# P_05__PMIC.net
KiCad netlist of a schematic drawn in Altium Designer
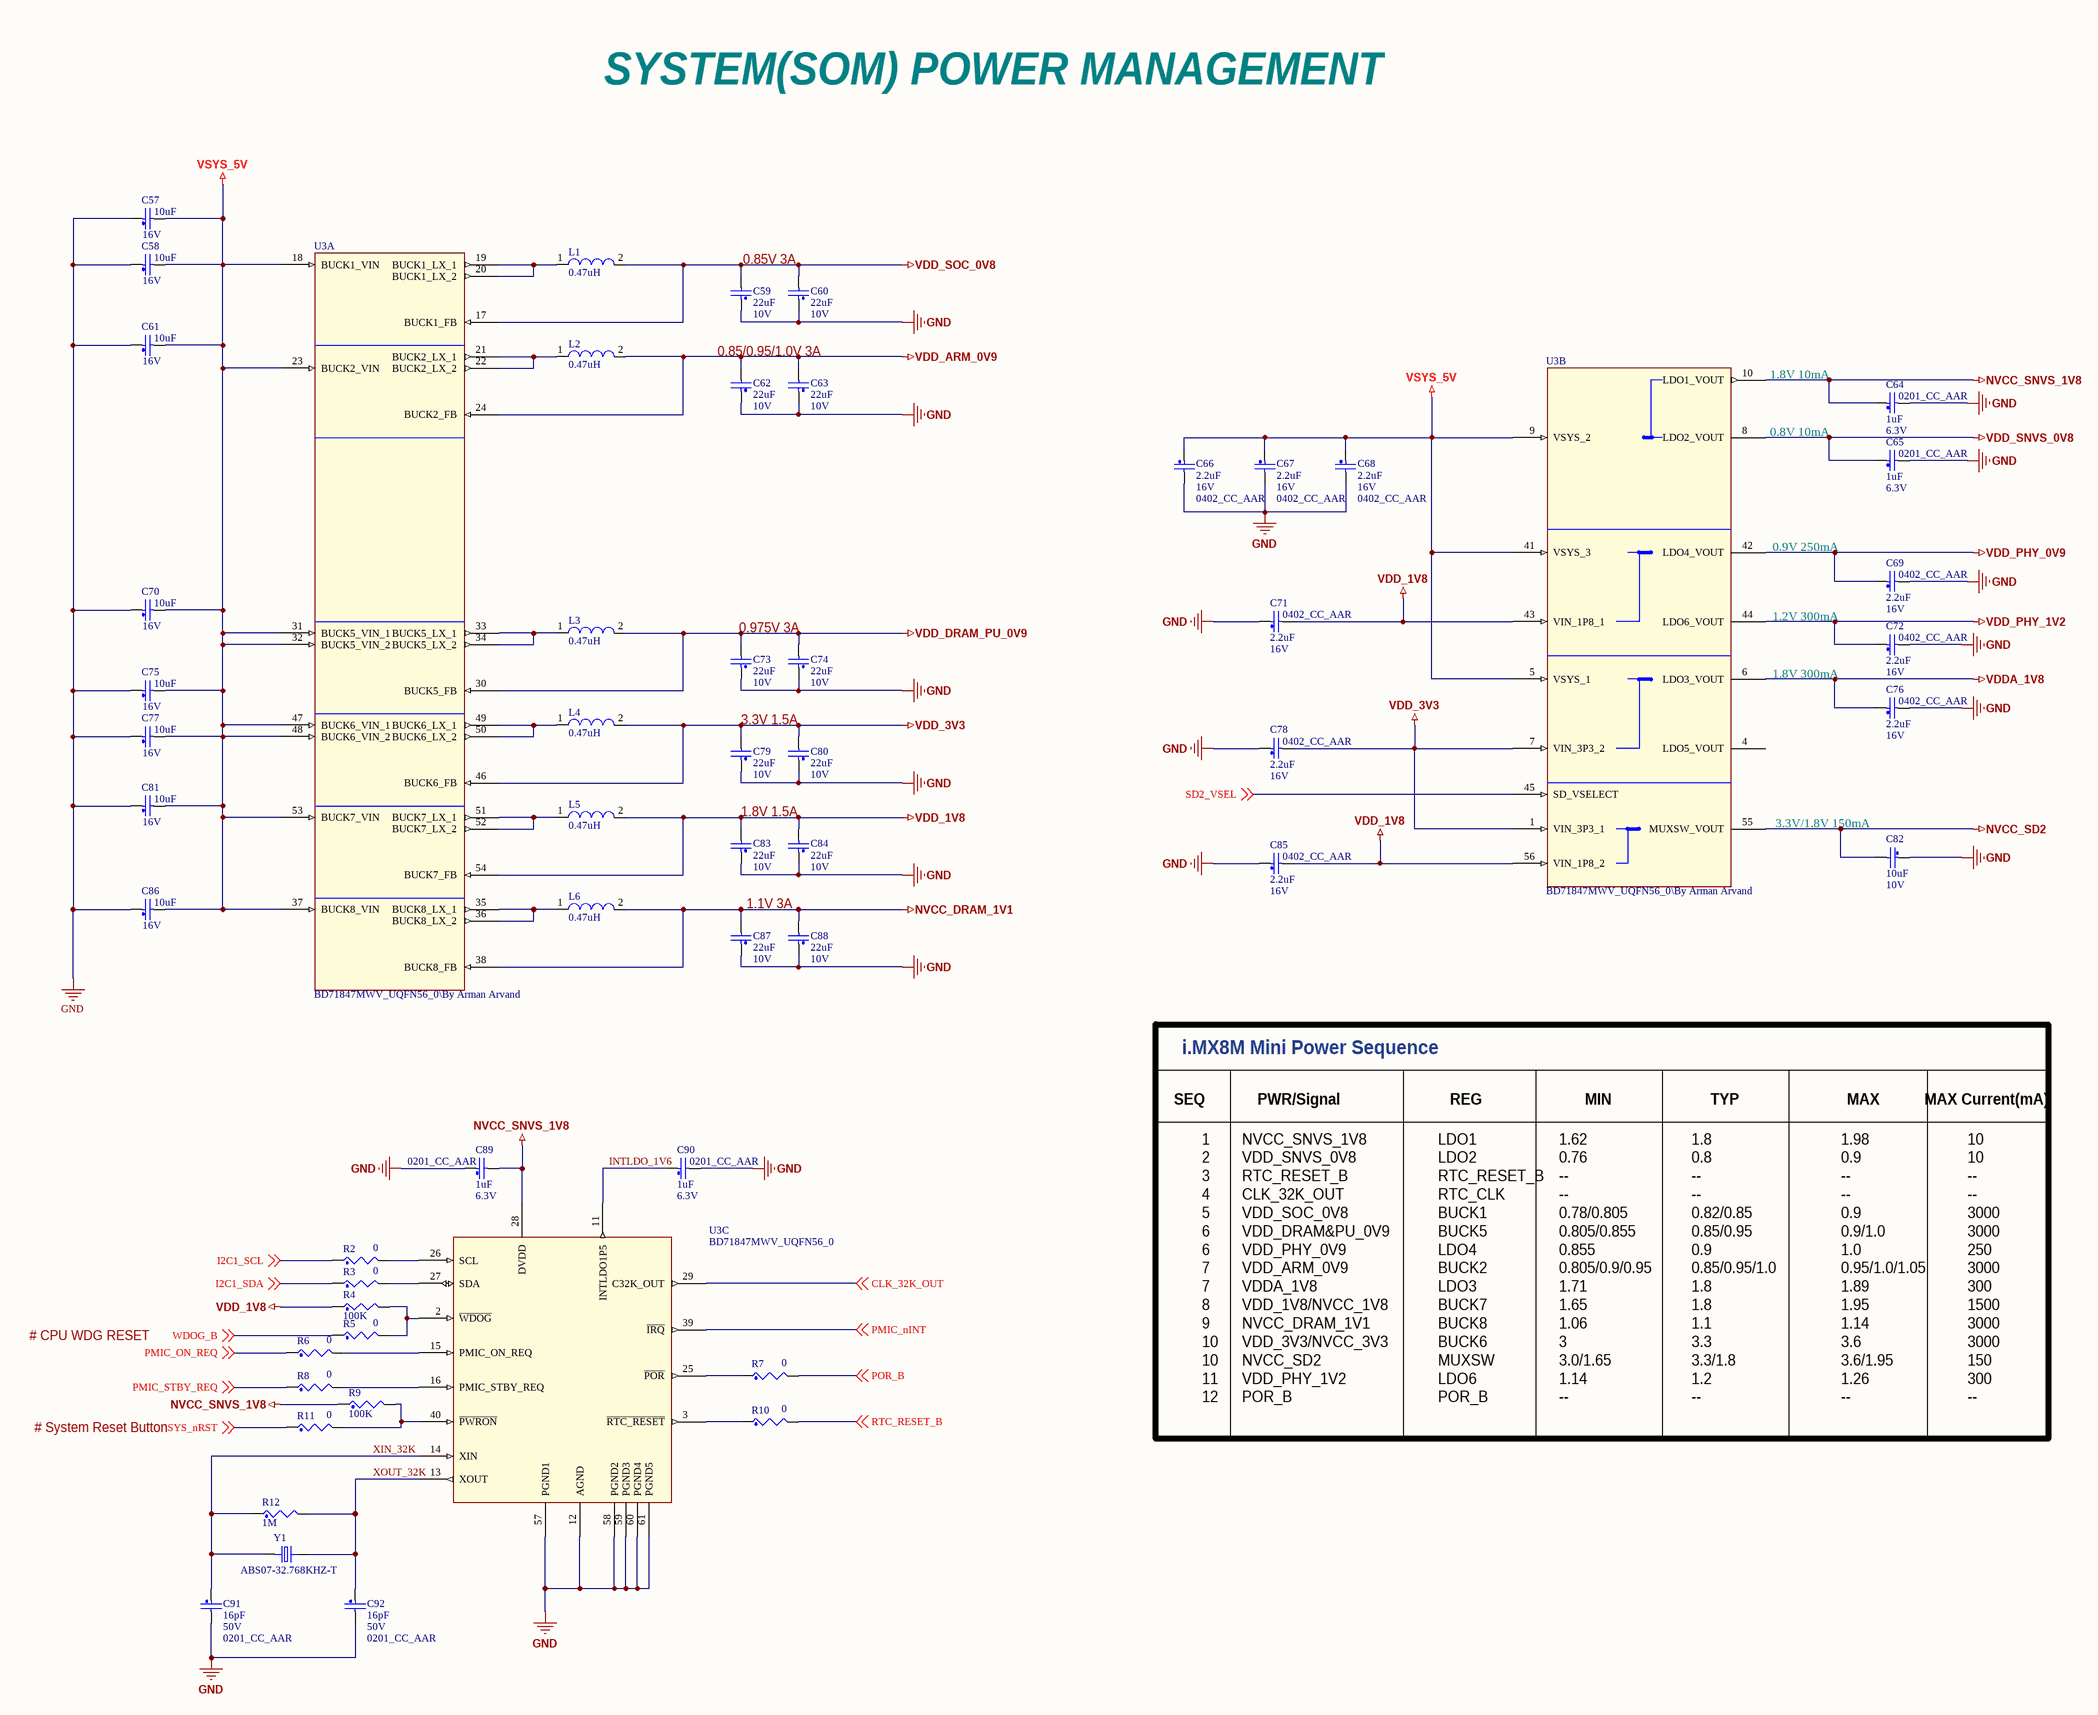
[diagram p0: P[05]_PMIC.SchDoc]

(export (version "E")
  (design (tool "Eeschema 10.0.6"))
  (components
    (comp (ref "C57")
      (value "10uF")
      (footprint "0603_CC")
      (fields (field (name "VOLTAGE") "16V"))
      (libsource (lib "AA_iMX8_M_") (part "CAP_NP"))
    )
    (comp (ref "C58")
      (value "10uF")
      (footprint "0603_CC")
      (fields (field (name "VOLTAGE") "16V"))
      (libsource (lib "AA_iMX8_M_") (part "CAP_NP"))
    )
    (comp (ref "C59")
      (value "22uF")
      (footprint "0603_CC")
      (fields (field (name "VOLTAGE") "10V"))
      (libsource (lib "AA_iMX8_M_") (part "CAP_NP"))
    )
    (comp (ref "C60")
      (value "22uF")
      (footprint "0603_CC")
      (fields (field (name "VOLTAGE") "10V"))
      (libsource (lib "AA_iMX8_M_") (part "CAP_NP"))
    )
    (comp (ref "C61")
      (value "10uF")
      (footprint "0603_CC")
      (fields (field (name "VOLTAGE") "16V"))
      (libsource (lib "AA_iMX8_M_") (part "CAP_NP"))
    )
    (comp (ref "C62")
      (value "22uF")
      (footprint "0603_CC")
      (fields (field (name "VOLTAGE") "10V"))
      (libsource (lib "AA_iMX8_M_") (part "CAP_NP"))
    )
    (comp (ref "C63")
      (value "22uF")
      (footprint "0603_CC")
      (fields (field (name "VOLTAGE") "10V"))
      (libsource (lib "AA_iMX8_M_") (part "CAP_NP"))
    )
    (comp (ref "C64")
      (value "1uF")
      (footprint "0201_CC_AAR")
      (fields (field (name "VOLTAGE") "6.3V"))
      (libsource (lib "AA_iMX8_M_") (part "CAP_NP"))
    )
    (comp (ref "C65")
      (value "1uF")
      (footprint "0201_CC_AAR")
      (fields (field (name "VOLTAGE") "6.3V"))
      (libsource (lib "AA_iMX8_M_") (part "CAP_NP"))
    )
    (comp (ref "C66")
      (value "2.2uF")
      (footprint "0402_CC_AAR")
      (fields (field (name "VOLTAGE") "16V"))
      (libsource (lib "AA_iMX8_M_") (part "CAP_NP"))
    )
    (comp (ref "C67")
      (value "2.2uF")
      (footprint "0402_CC_AAR")
      (fields (field (name "VOLTAGE") "16V"))
      (libsource (lib "AA_iMX8_M_") (part "CAP_NP"))
    )
    (comp (ref "C68")
      (value "2.2uF")
      (footprint "0402_CC_AAR")
      (fields (field (name "VOLTAGE") "16V"))
      (libsource (lib "AA_iMX8_M_") (part "CAP_NP"))
    )
    (comp (ref "C69")
      (value "2.2uF")
      (footprint "0402_CC_AAR")
      (fields (field (name "VOLTAGE") "16V"))
      (libsource (lib "AA_iMX8_M_") (part "CAP_NP"))
    )
    (comp (ref "C70")
      (value "10uF")
      (footprint "0603_CC")
      (fields (field (name "VOLTAGE") "16V"))
      (libsource (lib "AA_iMX8_M_") (part "CAP_NP"))
    )
    (comp (ref "C71")
      (value "2.2uF")
      (footprint "0402_CC_AAR")
      (fields (field (name "VOLTAGE") "16V"))
      (libsource (lib "AA_iMX8_M_") (part "CAP_NP"))
    )
    (comp (ref "C72")
      (value "2.2uF")
      (footprint "0402_CC_AAR")
      (fields (field (name "VOLTAGE") "16V"))
      (libsource (lib "AA_iMX8_M_") (part "CAP_NP"))
    )
    (comp (ref "C73")
      (value "22uF")
      (footprint "0603_CC")
      (fields (field (name "VOLTAGE") "10V"))
      (libsource (lib "AA_iMX8_M_") (part "CAP_NP"))
    )
    (comp (ref "C74")
      (value "22uF")
      (footprint "0603_CC")
      (fields (field (name "VOLTAGE") "10V"))
      (libsource (lib "AA_iMX8_M_") (part "CAP_NP"))
    )
    (comp (ref "C75")
      (value "10uF")
      (footprint "0603_CC")
      (fields (field (name "VOLTAGE") "16V"))
      (libsource (lib "AA_iMX8_M_") (part "CAP_NP"))
    )
    (comp (ref "C76")
      (value "2.2uF")
      (footprint "0402_CC_AAR")
      (fields (field (name "VOLTAGE") "16V"))
      (libsource (lib "AA_iMX8_M_") (part "CAP_NP"))
    )
    (comp (ref "C77")
      (value "10uF")
      (footprint "0603_CC")
      (fields (field (name "VOLTAGE") "16V"))
      (libsource (lib "AA_iMX8_M_") (part "CAP_NP"))
    )
    (comp (ref "C78")
      (value "2.2uF")
      (footprint "0402_CC_AAR")
      (fields (field (name "VOLTAGE") "16V"))
      (libsource (lib "AA_iMX8_M_") (part "CAP_NP"))
    )
    (comp (ref "C79")
      (value "22uF")
      (footprint "0603_CC")
      (fields (field (name "VOLTAGE") "10V"))
      (libsource (lib "AA_iMX8_M_") (part "CAP_NP"))
    )
    (comp (ref "C80")
      (value "22uF")
      (footprint "0603_CC")
      (fields (field (name "VOLTAGE") "10V"))
      (libsource (lib "AA_iMX8_M_") (part "CAP_NP"))
    )
    (comp (ref "C81")
      (value "10uF")
      (footprint "0603_CC")
      (fields (field (name "VOLTAGE") "16V"))
      (libsource (lib "AA_iMX8_M_") (part "CAP_NP"))
    )
    (comp (ref "C82")
      (value "10uF")
      (footprint "0603_CC")
      (fields (field (name "VOLTAGE") "10V"))
      (libsource (lib "AA_iMX8_M_") (part "CAP_NP"))
    )
    (comp (ref "C83")
      (value "22uF")
      (footprint "0603_CC")
      (fields (field (name "VOLTAGE") "10V"))
      (libsource (lib "AA_iMX8_M_") (part "CAP_NP"))
    )
    (comp (ref "C84")
      (value "22uF")
      (footprint "0603_CC")
      (fields (field (name "VOLTAGE") "10V"))
      (libsource (lib "AA_iMX8_M_") (part "CAP_NP"))
    )
    (comp (ref "C85")
      (value "2.2uF")
      (footprint "0402_CC_AAR")
      (fields (field (name "VOLTAGE") "16V"))
      (libsource (lib "AA_iMX8_M_") (part "CAP_NP"))
    )
    (comp (ref "C86")
      (value "10uF")
      (footprint "0603_CC")
      (fields (field (name "VOLTAGE") "16V"))
      (libsource (lib "AA_iMX8_M_") (part "CAP_NP"))
    )
    (comp (ref "C87")
      (value "22uF")
      (footprint "0603_CC")
      (fields (field (name "VOLTAGE") "10V"))
      (libsource (lib "AA_iMX8_M_") (part "CAP_NP"))
    )
    (comp (ref "C88")
      (value "22uF")
      (footprint "0603_CC")
      (fields (field (name "VOLTAGE") "10V"))
      (libsource (lib "AA_iMX8_M_") (part "CAP_NP"))
    )
    (comp (ref "C89")
      (value "1uF")
      (footprint "0201_CC_AAR")
      (fields (field (name "VOLTAGE") "6.3V"))
      (libsource (lib "AA_iMX8_M_") (part "CAP_NP"))
    )
    (comp (ref "C90")
      (value "1uF")
      (footprint "0201_CC_AAR")
      (fields (field (name "VOLTAGE") "6.3V"))
      (libsource (lib "AA_iMX8_M_") (part "CAP_NP"))
    )
    (comp (ref "C91")
      (value "16pF")
      (footprint "0201_CC_AAR")
      (fields (field (name "VOLTAGE") "50V"))
      (libsource (lib "AA_iMX8_M_") (part "CAP_NP"))
    )
    (comp (ref "C92")
      (value "16pF")
      (footprint "0201_CC_AAR")
      (fields (field (name "VOLTAGE") "50V"))
      (libsource (lib "AA_iMX8_M_") (part "CAP_NP"))
    )
    (comp (ref "L1")
      (value "0.47uH")
      (footprint "IND_SPH2520")
      (libsource (lib "AA_iMX8_M_") (part "INDUCTOR"))
    )
    (comp (ref "L2")
      (value "0.47uH")
      (footprint "IND_SPH2520")
      (libsource (lib "AA_iMX8_M_") (part "INDUCTOR"))
    )
    (comp (ref "L3")
      (value "0.47uH")
      (footprint "IND_SPH2520")
      (libsource (lib "AA_iMX8_M_") (part "INDUCTOR"))
    )
    (comp (ref "L4")
      (value "0.47uH")
      (footprint "IND_SPH2520")
      (libsource (lib "AA_iMX8_M_") (part "INDUCTOR"))
    )
    (comp (ref "L5")
      (value "0.47uH")
      (footprint "IND_SPH2520")
      (libsource (lib "AA_iMX8_M_") (part "INDUCTOR"))
    )
    (comp (ref "L6")
      (value "0.47uH")
      (footprint "IND_SPH2520")
      (libsource (lib "AA_iMX8_M_") (part "INDUCTOR"))
    )
    (comp (ref "R2") (value "0") (footprint "0402_CC") (libsource (lib "AA_iMX8_M_") (part "RES")))
    (comp (ref "R3") (value "0") (footprint "0402_CC") (libsource (lib "AA_iMX8_M_") (part "RES")))
    (comp (ref "R4") (value "100K") (footprint "0201_CC") (libsource (lib "AA_iMX8_M_") (part "RES")))
    (comp (ref "R5") (value "0") (footprint "0402_CC") (libsource (lib "AA_iMX8_M_") (part "RES")))
    (comp (ref "R6") (value "0") (footprint "0402_CC") (libsource (lib "AA_iMX8_M_") (part "RES")))
    (comp (ref "R7") (value "0") (footprint "0402_CC") (libsource (lib "AA_iMX8_M_") (part "RES")))
    (comp (ref "R8") (value "0") (footprint "0402_CC") (libsource (lib "AA_iMX8_M_") (part "RES")))
    (comp (ref "R9") (value "100K") (footprint "0201_CC") (libsource (lib "AA_iMX8_M_") (part "RES")))
    (comp (ref "R10") (value "0") (footprint "0402_CC") (libsource (lib "AA_iMX8_M_") (part "RES")))
    (comp (ref "R11") (value "0") (footprint "0402_CC") (libsource (lib "AA_iMX8_M_") (part "RES")))
    (comp (ref "R12") (value "1M") (footprint "0201_CC") (libsource (lib "AA_iMX8_M_") (part "RES")))
    (comp (ref "U3")
      (value "BD71847MWV_UQFN56_~{0}By Arman Arvand")
      (footprint "UQFN56_0P4_7X7_EP_S185")
      (description "BD71847MWV_UQFN56_0\\By Arman Arvand")
      (libsource (lib "AA_iMX8_M_") (part "BD71847MWV_UQFN56_0"))
    )
    (comp (ref "Y1")
      (value "ABS07-32.768KHZ-T")
      (footprint "XTAL_ABS07-32.768KHZ-T")
      (description "32.768kHz Â±20ppm Crystal 12.5pF 70 kOhms 2-SMD, No Lead")
      (fields (field (name "MF") "Abracon LLC") (field (name "MP") "ABS07-32.768KHZ"))
      (libsource (lib "AA_iMX8_M_") (part "ABS07-32.768KHZ-T"))
    )
  )
  (nets
    (net (code "1") (name "/INTLDO_1V6") (class "Default")
      (node (ref "C90") (pin "1") (pinfunction "1_1") (pintype "passive"))
      (node (ref "U3") (pin "11") (pinfunction "INTLDO1P5_11") (pintype "output"))
    )
    (net (code "2") (name "/XIN_32K") (class "Default")
      (node (ref "C91") (pin "1") (pinfunction "1_1") (pintype "passive"))
      (node (ref "R12") (pin "1") (pinfunction "1_1") (pintype "passive"))
      (node (ref "U3") (pin "14") (pinfunction "XIN_14") (pintype "input"))
      (node (ref "Y1") (pin "1") (pinfunction "1_1") (pintype "passive"))
    )
    (net (code "3") (name "/XOUT_32K") (class "Default")
      (node (ref "C92") (pin "1") (pinfunction "1_1") (pintype "passive"))
      (node (ref "R12") (pin "2") (pinfunction "2_2") (pintype "passive"))
      (node (ref "U3") (pin "13") (pinfunction "XOUT_13") (pintype "output"))
      (node (ref "Y1") (pin "2") (pinfunction "2_2") (pintype "passive"))
    )
    (net (code "4") (name "CLK_32K_OUT") (class "Default")
      (node (ref "U3") (pin "29") (pinfunction "C32K_OUT_29") (pintype "output"))
    )
    (net (code "5") (name "GND") (class "Default")
      (node (ref "C57") (pin "1") (pinfunction "1_1") (pintype "passive"))
      (node (ref "C58") (pin "1") (pinfunction "1_1") (pintype "passive"))
      (node (ref "C59") (pin "1") (pinfunction "1_1") (pintype "passive"))
      (node (ref "C60") (pin "1") (pinfunction "1_1") (pintype "passive"))
      (node (ref "C61") (pin "1") (pinfunction "1_1") (pintype "passive"))
      (node (ref "C62") (pin "1") (pinfunction "1_1") (pintype "passive"))
      (node (ref "C63") (pin "1") (pinfunction "1_1") (pintype "passive"))
      (node (ref "C64") (pin "2") (pinfunction "2_2") (pintype "passive"))
      (node (ref "C65") (pin "2") (pinfunction "2_2") (pintype "passive"))
      (node (ref "C66") (pin "2") (pinfunction "2_2") (pintype "passive"))
      (node (ref "C67") (pin "2") (pinfunction "2_2") (pintype "passive"))
      (node (ref "C68") (pin "2") (pinfunction "2_2") (pintype "passive"))
      (node (ref "C69") (pin "2") (pinfunction "2_2") (pintype "passive"))
      (node (ref "C70") (pin "1") (pinfunction "1_1") (pintype "passive"))
      (node (ref "C71") (pin "1") (pinfunction "1_1") (pintype "passive"))
      (node (ref "C72") (pin "2") (pinfunction "2_2") (pintype "passive"))
      (node (ref "C73") (pin "1") (pinfunction "1_1") (pintype "passive"))
      (node (ref "C74") (pin "1") (pinfunction "1_1") (pintype "passive"))
      (node (ref "C75") (pin "1") (pinfunction "1_1") (pintype "passive"))
      (node (ref "C76") (pin "2") (pinfunction "2_2") (pintype "passive"))
      (node (ref "C77") (pin "1") (pinfunction "1_1") (pintype "passive"))
      (node (ref "C78") (pin "1") (pinfunction "1_1") (pintype "passive"))
      (node (ref "C79") (pin "1") (pinfunction "1_1") (pintype "passive"))
      (node (ref "C80") (pin "1") (pinfunction "1_1") (pintype "passive"))
      (node (ref "C81") (pin "1") (pinfunction "1_1") (pintype "passive"))
      (node (ref "C82") (pin "1") (pinfunction "1_1") (pintype "passive"))
      (node (ref "C83") (pin "1") (pinfunction "1_1") (pintype "passive"))
      (node (ref "C84") (pin "1") (pinfunction "1_1") (pintype "passive"))
      (node (ref "C85") (pin "1") (pinfunction "1_1") (pintype "passive"))
      (node (ref "C86") (pin "1") (pinfunction "1_1") (pintype "passive"))
      (node (ref "C87") (pin "1") (pinfunction "1_1") (pintype "passive"))
      (node (ref "C88") (pin "1") (pinfunction "1_1") (pintype "passive"))
      (node (ref "C89") (pin "1") (pinfunction "1_1") (pintype "passive"))
      (node (ref "C90") (pin "2") (pinfunction "2_2") (pintype "passive"))
      (node (ref "C91") (pin "2") (pinfunction "2_2") (pintype "passive"))
      (node (ref "C92") (pin "2") (pinfunction "2_2") (pintype "passive"))
      (node (ref "U3") (pin "12") (pinfunction "AGND_12") (pintype "power_in"))
      (node (ref "U3") (pin "57") (pinfunction "PGND1_57") (pintype "power_in"))
      (node (ref "U3") (pin "58") (pinfunction "PGND2_58") (pintype "power_in"))
      (node (ref "U3") (pin "59") (pinfunction "PGND3_59") (pintype "power_in"))
      (node (ref "U3") (pin "60") (pinfunction "PGND4_60") (pintype "power_in"))
      (node (ref "U3") (pin "61") (pinfunction "PGND5_61") (pintype "power_in"))
    )
    (net (code "6") (name "I2C1_SCL") (class "Default")
      (node (ref "R2") (pin "1") (pinfunction "1_1") (pintype "passive"))
    )
    (net (code "7") (name "I2C1_SDA") (class "Default")
      (node (ref "R3") (pin "1") (pinfunction "1_1") (pintype "passive"))
    )
    (net (code "8") (name "NVCC_DRAM_1V1") (class "Default")
      (node (ref "C87") (pin "2") (pinfunction "2_2") (pintype "passive"))
      (node (ref "C88") (pin "2") (pinfunction "2_2") (pintype "passive"))
      (node (ref "L6") (pin "2") (pinfunction "2_2") (pintype "passive"))
      (node (ref "U3") (pin "38") (pinfunction "BUCK8_FB_38") (pintype "input"))
    )
    (net (code "9") (name "NVCC_SD2") (class "Default")
      (node (ref "C82") (pin "2") (pinfunction "2_2") (pintype "passive"))
      (node (ref "U3") (pin "55") (pinfunction "MUXSW_VOUT_55") (pintype "power_in"))
    )
    (net (code "10") (name "NVCC_SNVS_1V8") (class "Default")
      (node (ref "C64") (pin "1") (pinfunction "1_1") (pintype "passive"))
      (node (ref "C89") (pin "2") (pinfunction "2_2") (pintype "passive"))
      (node (ref "R9") (pin "1") (pinfunction "1_1") (pintype "passive"))
      (node (ref "U3") (pin "10") (pinfunction "LDO1_VOUT_10") (pintype "output"))
      (node (ref "U3") (pin "28") (pinfunction "DVDD_28") (pintype "power_in"))
    )
    (net (code "11") (name "Net-(U3A-BUCK1_LX_1)") (class "Default")
      (node (ref "L1") (pin "1") (pinfunction "1_1") (pintype "passive"))
      (node (ref "U3") (pin "19") (pinfunction "BUCK1_LX_1_19") (pintype "output"))
      (node (ref "U3") (pin "20") (pinfunction "BUCK1_LX_2_20") (pintype "output"))
    )
    (net (code "12") (name "Net-(U3A-BUCK2_LX_1)") (class "Default")
      (node (ref "L2") (pin "1") (pinfunction "1_1") (pintype "passive"))
      (node (ref "U3") (pin "21") (pinfunction "BUCK2_LX_1_21") (pintype "output"))
      (node (ref "U3") (pin "22") (pinfunction "BUCK2_LX_2_22") (pintype "output"))
    )
    (net (code "13") (name "Net-(U3A-BUCK5_LX_1)") (class "Default")
      (node (ref "L3") (pin "1") (pinfunction "1_1") (pintype "passive"))
      (node (ref "U3") (pin "33") (pinfunction "BUCK5_LX_1_33") (pintype "output"))
      (node (ref "U3") (pin "34") (pinfunction "BUCK5_LX_2_34") (pintype "output"))
    )
    (net (code "14") (name "Net-(U3A-BUCK6_LX_1)") (class "Default")
      (node (ref "L4") (pin "1") (pinfunction "1_1") (pintype "passive"))
      (node (ref "U3") (pin "49") (pinfunction "BUCK6_LX_1_49") (pintype "output"))
      (node (ref "U3") (pin "50") (pinfunction "BUCK6_LX_2_50") (pintype "output"))
    )
    (net (code "15") (name "Net-(U3A-BUCK7_LX_1)") (class "Default")
      (node (ref "L5") (pin "1") (pinfunction "1_1") (pintype "passive"))
      (node (ref "U3") (pin "51") (pinfunction "BUCK7_LX_1_51") (pintype "output"))
      (node (ref "U3") (pin "52") (pinfunction "BUCK7_LX_2_52") (pintype "output"))
    )
    (net (code "16") (name "Net-(U3A-BUCK8_LX_1)") (class "Default")
      (node (ref "L6") (pin "1") (pinfunction "1_1") (pintype "passive"))
      (node (ref "U3") (pin "35") (pinfunction "BUCK8_LX_1_35") (pintype "output"))
      (node (ref "U3") (pin "36") (pinfunction "BUCK8_LX_2_36") (pintype "output"))
    )
    (net (code "17") (name "Net-(U3C-PMIC_ON_REQ)") (class "Default")
      (node (ref "R6") (pin "2") (pinfunction "2_2") (pintype "passive"))
      (node (ref "U3") (pin "15") (pinfunction "PMIC_ON_REQ_15") (pintype "input"))
    )
    (net (code "18") (name "Net-(U3C-PMIC_STBY_REQ)") (class "Default")
      (node (ref "R8") (pin "2") (pinfunction "2_2") (pintype "passive"))
      (node (ref "U3") (pin "16") (pinfunction "PMIC_STBY_REQ_16") (pintype "input"))
    )
    (net (code "19") (name "Net-(U3C-SCL)") (class "Default")
      (node (ref "R2") (pin "2") (pinfunction "2_2") (pintype "passive"))
      (node (ref "U3") (pin "26") (pinfunction "SCL_26") (pintype "input"))
    )
    (net (code "20") (name "Net-(U3C-SDA)") (class "Default")
      (node (ref "R3") (pin "2") (pinfunction "2_2") (pintype "passive"))
      (node (ref "U3") (pin "27") (pinfunction "SDA_27") (pintype "bidirectional"))
    )
    (net (code "21") (name "Net-(U3C-~{POR})") (class "Default")
      (node (ref "R7") (pin "1") (pinfunction "1_1") (pintype "passive"))
      (node (ref "U3") (pin "25") (pinfunction "~{POR}_25") (pintype "output"))
    )
    (net (code "22") (name "Net-(U3C-~{PWRON})") (class "Default")
      (node (ref "R11") (pin "2") (pinfunction "2_2") (pintype "passive"))
      (node (ref "R9") (pin "2") (pinfunction "2_2") (pintype "passive"))
      (node (ref "U3") (pin "40") (pinfunction "~{PWRON}_40") (pintype "input"))
    )
    (net (code "23") (name "Net-(U3C-~{RTC_RESET})") (class "Default")
      (node (ref "R10") (pin "1") (pinfunction "1_1") (pintype "passive"))
      (node (ref "U3") (pin "3") (pinfunction "~{RTC_RESET}_3") (pintype "output"))
    )
    (net (code "24") (name "Net-(U3C-~{WDOG})") (class "Default")
      (node (ref "R4") (pin "2") (pinfunction "2_2") (pintype "passive"))
      (node (ref "R5") (pin "2") (pinfunction "2_2") (pintype "passive"))
      (node (ref "U3") (pin "2") (pinfunction "~{WDOG}_2") (pintype "input"))
    )
    (net (code "25") (name "PMIC_ON_REQ") (class "Default")
      (node (ref "R6") (pin "1") (pinfunction "1_1") (pintype "passive"))
    )
    (net (code "26") (name "PMIC_STBY_REQ") (class "Default")
      (node (ref "R8") (pin "1") (pinfunction "1_1") (pintype "passive"))
    )
    (net (code "27") (name "PMIC_nINT") (class "Default")
      (node (ref "U3") (pin "39") (pinfunction "~{IRQ}_39") (pintype "output"))
    )
    (net (code "28") (name "POR_B") (class "Default")
      (node (ref "R7") (pin "2") (pinfunction "2_2") (pintype "passive"))
    )
    (net (code "29") (name "RTC_RESET_B") (class "Default")
      (node (ref "R10") (pin "2") (pinfunction "2_2") (pintype "passive"))
    )
    (net (code "30") (name "SD2_VSEL") (class "Default")
      (node (ref "U3") (pin "45") (pinfunction "SD_VSELECT_45") (pintype "input"))
    )
    (net (code "31") (name "SYS_nRST") (class "Default")
      (node (ref "R11") (pin "1") (pinfunction "1_1") (pintype "passive"))
    )
    (net (code "32") (name "VDDA_1V8") (class "Default")
      (node (ref "C76") (pin "1") (pinfunction "1_1") (pintype "passive"))
      (node (ref "U3") (pin "6") (pinfunction "LDO3_VOUT_6") (pintype "power_in"))
    )
    (net (code "33") (name "VDD_1V8") (class "Default")
      (node (ref "C71") (pin "2") (pinfunction "2_2") (pintype "passive"))
      (node (ref "C83") (pin "2") (pinfunction "2_2") (pintype "passive"))
      (node (ref "C84") (pin "2") (pinfunction "2_2") (pintype "passive"))
      (node (ref "C85") (pin "2") (pinfunction "2_2") (pintype "passive"))
      (node (ref "L5") (pin "2") (pinfunction "2_2") (pintype "passive"))
      (node (ref "R4") (pin "1") (pinfunction "1_1") (pintype "passive"))
      (node (ref "U3") (pin "43") (pinfunction "VIN_1P8_1_43") (pintype "input"))
      (node (ref "U3") (pin "54") (pinfunction "BUCK7_FB_54") (pintype "input"))
      (node (ref "U3") (pin "56") (pinfunction "VIN_1P8_2_56") (pintype "input"))
    )
    (net (code "34") (name "VDD_3V3") (class "Default")
      (node (ref "C78") (pin "2") (pinfunction "2_2") (pintype "passive"))
      (node (ref "C79") (pin "2") (pinfunction "2_2") (pintype "passive"))
      (node (ref "C80") (pin "2") (pinfunction "2_2") (pintype "passive"))
      (node (ref "L4") (pin "2") (pinfunction "2_2") (pintype "passive"))
      (node (ref "U3") (pin "1") (pinfunction "VIN_3P3_1_1") (pintype "input"))
      (node (ref "U3") (pin "46") (pinfunction "BUCK6_FB_46") (pintype "input"))
      (node (ref "U3") (pin "7") (pinfunction "VIN_3P3_2_7") (pintype "input"))
    )
    (net (code "35") (name "VDD_ARM_0V9") (class "Default")
      (node (ref "C62") (pin "2") (pinfunction "2_2") (pintype "passive"))
      (node (ref "C63") (pin "2") (pinfunction "2_2") (pintype "passive"))
      (node (ref "L2") (pin "2") (pinfunction "2_2") (pintype "passive"))
      (node (ref "U3") (pin "24") (pinfunction "BUCK2_FB_24") (pintype "input"))
    )
    (net (code "36") (name "VDD_DRAM_PU_0V9") (class "Default")
      (node (ref "C73") (pin "2") (pinfunction "2_2") (pintype "passive"))
      (node (ref "C74") (pin "2") (pinfunction "2_2") (pintype "passive"))
      (node (ref "L3") (pin "2") (pinfunction "2_2") (pintype "passive"))
      (node (ref "U3") (pin "30") (pinfunction "BUCK5_FB_30") (pintype "input"))
    )
    (net (code "37") (name "VDD_PHY_0V9") (class "Default")
      (node (ref "C69") (pin "1") (pinfunction "1_1") (pintype "passive"))
      (node (ref "U3") (pin "42") (pinfunction "LDO4_VOUT_42") (pintype "power_in"))
    )
    (net (code "38") (name "VDD_PHY_1V2") (class "Default")
      (node (ref "C72") (pin "1") (pinfunction "1_1") (pintype "passive"))
      (node (ref "U3") (pin "44") (pinfunction "LDO6_VOUT_44") (pintype "power_in"))
    )
    (net (code "39") (name "VDD_SNVS_0V8") (class "Default")
      (node (ref "C65") (pin "1") (pinfunction "1_1") (pintype "passive"))
      (node (ref "U3") (pin "8") (pinfunction "LDO2_VOUT_8") (pintype "power_in"))
    )
    (net (code "40") (name "VDD_SOC_0V8") (class "Default")
      (node (ref "C59") (pin "2") (pinfunction "2_2") (pintype "passive"))
      (node (ref "C60") (pin "2") (pinfunction "2_2") (pintype "passive"))
      (node (ref "L1") (pin "2") (pinfunction "2_2") (pintype "passive"))
      (node (ref "U3") (pin "17") (pinfunction "BUCK1_FB_17") (pintype "input"))
    )
    (net (code "41") (name "VSYS_5V") (class "Default")
      (node (ref "C57") (pin "2") (pinfunction "2_2") (pintype "passive"))
      (node (ref "C58") (pin "2") (pinfunction "2_2") (pintype "passive"))
      (node (ref "C61") (pin "2") (pinfunction "2_2") (pintype "passive"))
      (node (ref "C66") (pin "1") (pinfunction "1_1") (pintype "passive"))
      (node (ref "C67") (pin "1") (pinfunction "1_1") (pintype "passive"))
      (node (ref "C68") (pin "1") (pinfunction "1_1") (pintype "passive"))
      (node (ref "C70") (pin "2") (pinfunction "2_2") (pintype "passive"))
      (node (ref "C75") (pin "2") (pinfunction "2_2") (pintype "passive"))
      (node (ref "C77") (pin "2") (pinfunction "2_2") (pintype "passive"))
      (node (ref "C81") (pin "2") (pinfunction "2_2") (pintype "passive"))
      (node (ref "C86") (pin "2") (pinfunction "2_2") (pintype "passive"))
      (node (ref "U3") (pin "18") (pinfunction "BUCK1_VIN_18") (pintype "input"))
      (node (ref "U3") (pin "23") (pinfunction "BUCK2_VIN_23") (pintype "input"))
      (node (ref "U3") (pin "31") (pinfunction "BUCK5_VIN_1_31") (pintype "input"))
      (node (ref "U3") (pin "32") (pinfunction "BUCK5_VIN_2_32") (pintype "input"))
      (node (ref "U3") (pin "37") (pinfunction "BUCK8_VIN_37") (pintype "input"))
      (node (ref "U3") (pin "41") (pinfunction "VSYS_3_41") (pintype "input"))
      (node (ref "U3") (pin "47") (pinfunction "BUCK6_VIN_1_47") (pintype "input"))
      (node (ref "U3") (pin "48") (pinfunction "BUCK6_VIN_2_48") (pintype "input"))
      (node (ref "U3") (pin "5") (pinfunction "VSYS_1_5") (pintype "input"))
      (node (ref "U3") (pin "53") (pinfunction "BUCK7_VIN_53") (pintype "input"))
      (node (ref "U3") (pin "9") (pinfunction "VSYS_2_9") (pintype "input"))
    )
    (net (code "42") (name "WDOG_B") (class "Default")
      (node (ref "R5") (pin "1") (pinfunction "1_1") (pintype "passive"))
    )
    (net (code "43") (name "unconnected-(U3B-LDO5_VOUT-Pad4)") (class "Default")
      (node (ref "U3") (pin "4") (pinfunction "LDO5_VOUT_4") (pintype "power_in"))
    )
  )
)
